# powerboard.net
KiCad netlist of a schematic drawn in EAGLE
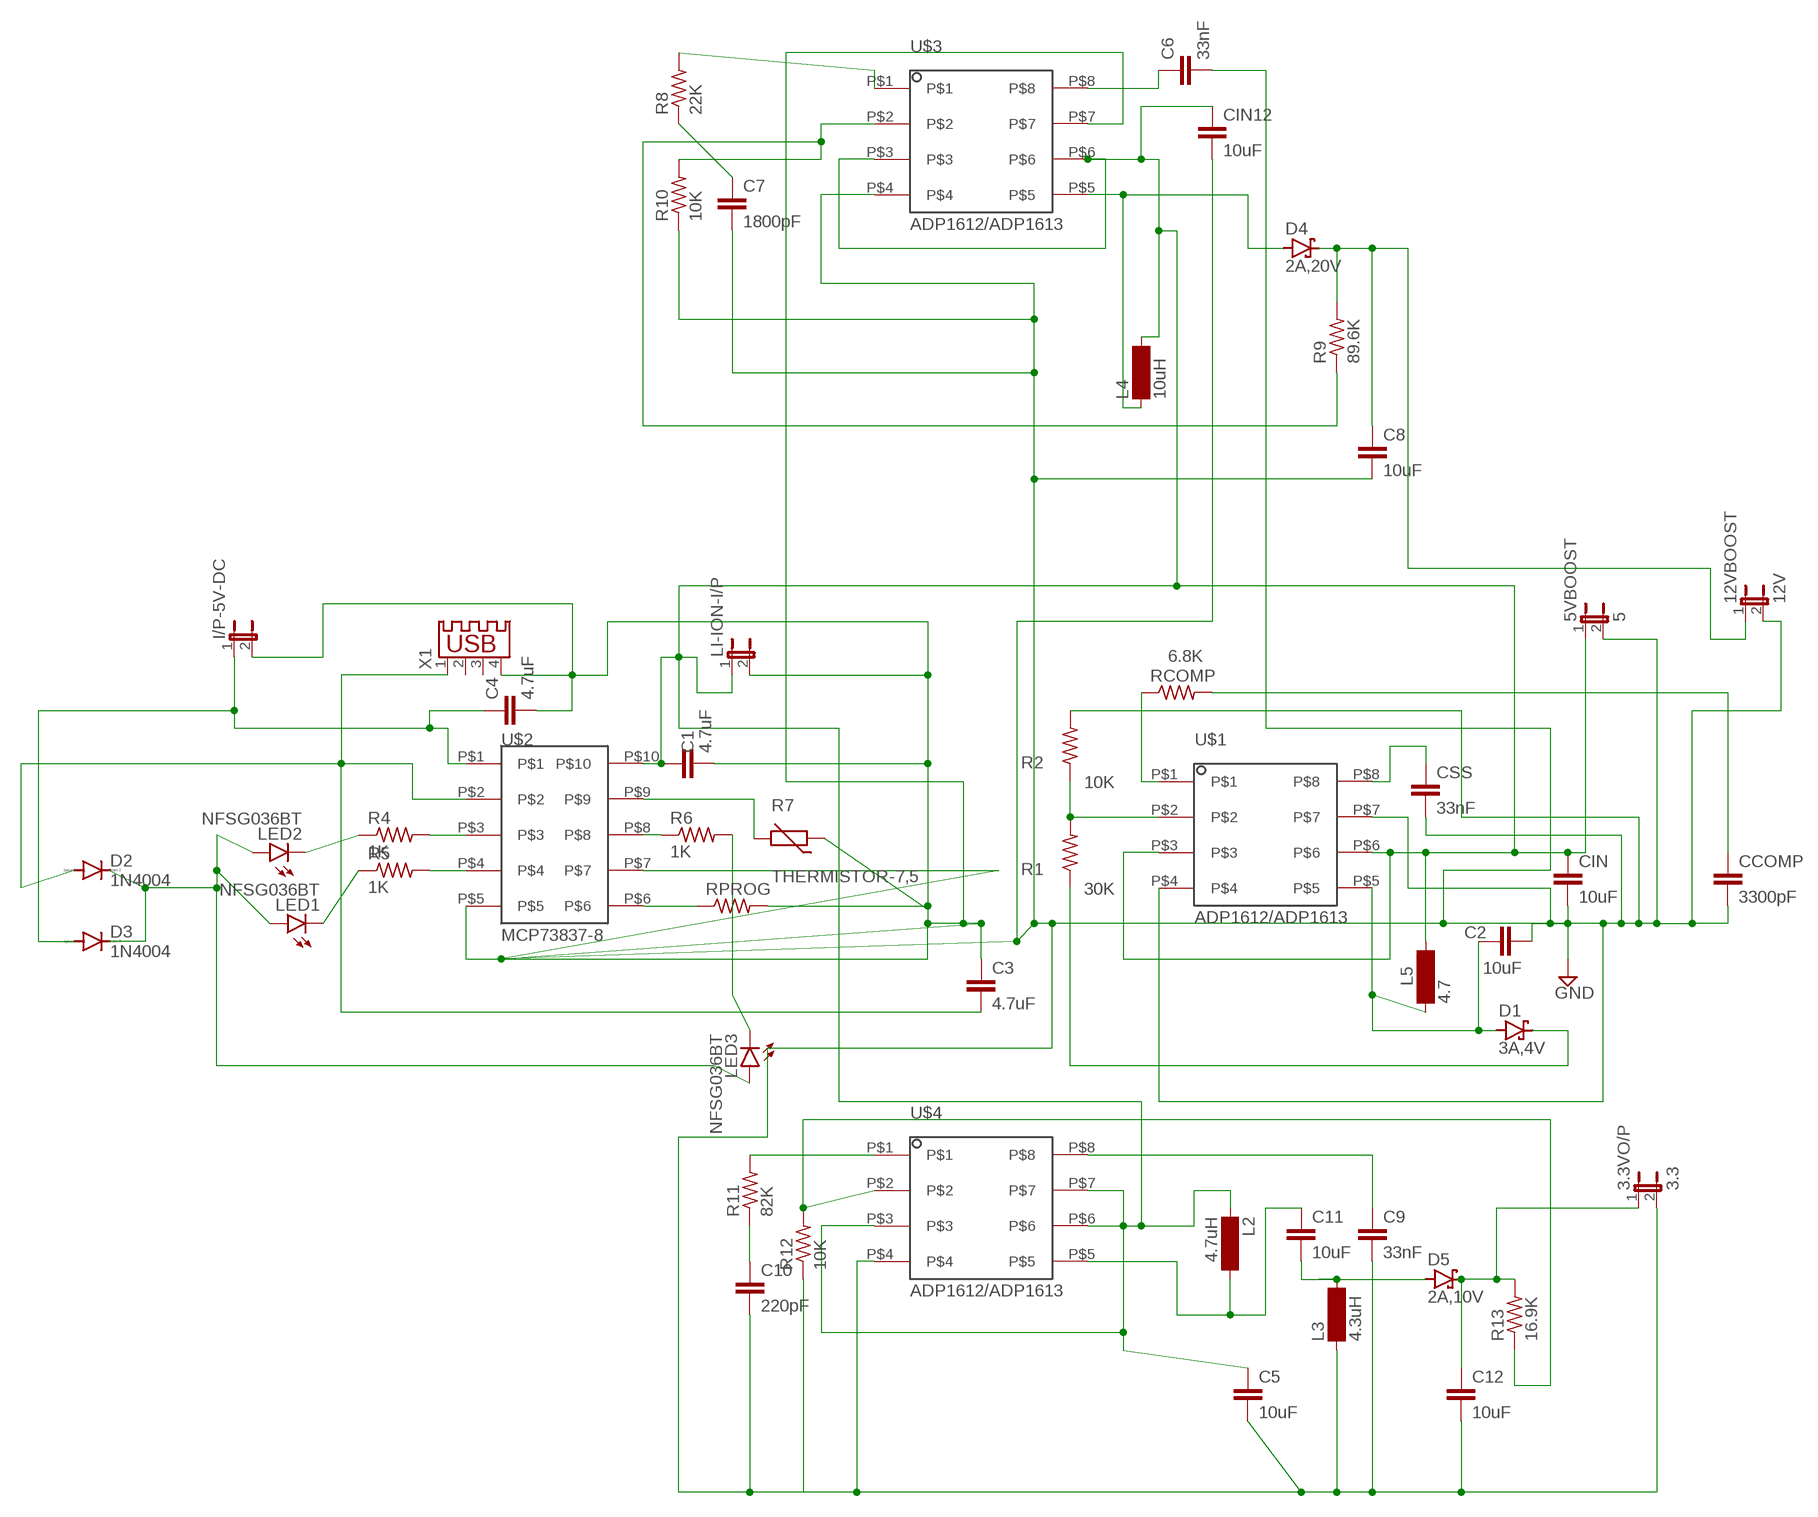
[diagram p0: schematic, sheet 1]

(export (version "E")
  (design (tool "Eeschema 10.0.6"))
  (components
    (comp (ref "3.3VO/P")
      (value "3.3")
      (footprint "eagle-import:JP1")
      (libsource (lib "eagle-import") (part "JP1E"))
    )
    (comp (ref "5VBOOST")
      (value "5")
      (footprint "eagle-import:JP1")
      (libsource (lib "eagle-import") (part "JP1E"))
    )
    (comp (ref "12VBOOST")
      (value "12V")
      (footprint "eagle-import:JP1")
      (libsource (lib "eagle-import") (part "JP1E"))
    )
    (comp (ref "C1")
      (value "4.7uF")
      (footprint "eagle-import:C2.5-3")
      (libsource (lib "eagle-import") (part "C2,5-3"))
    )
    (comp (ref "C2")
      (value "10uF")
      (footprint "eagle-import:C2.5-2")
      (libsource (lib "eagle-import") (part "C2.5/2"))
    )
    (comp (ref "C3")
      (value "4.7uF")
      (footprint "eagle-import:C2.5-3")
      (libsource (lib "eagle-import") (part "C2,5-3"))
    )
    (comp (ref "C4")
      (value "4.7uF")
      (footprint "eagle-import:C2.5-3")
      (libsource (lib "eagle-import") (part "C2,5-3"))
    )
    (comp (ref "C5")
      (value "10uF")
      (footprint "eagle-import:C2.5-2")
      (libsource (lib "eagle-import") (part "C2.5/2"))
    )
    (comp (ref "C6")
      (value "33nF")
      (footprint "eagle-import:C2.5-3")
      (libsource (lib "eagle-import") (part "C2,5-3"))
    )
    (comp (ref "C7")
      (value "1800pF")
      (footprint "eagle-import:C2.5-3")
      (libsource (lib "eagle-import") (part "C2,5-3"))
    )
    (comp (ref "C8")
      (value "10uF")
      (footprint "eagle-import:C2.5-3")
      (libsource (lib "eagle-import") (part "C2,5-3"))
    )
    (comp (ref "C9")
      (value "33nF")
      (footprint "eagle-import:C2.5-2")
      (libsource (lib "eagle-import") (part "C2.5/2"))
    )
    (comp (ref "C10")
      (value "220pF")
      (footprint "eagle-import:C2.5-2")
      (libsource (lib "eagle-import") (part "C2.5/2"))
    )
    (comp (ref "C11")
      (value "10uF")
      (footprint "eagle-import:C2.5-2")
      (libsource (lib "eagle-import") (part "C2.5/2"))
    )
    (comp (ref "C12")
      (value "10uF")
      (footprint "eagle-import:C2.5-2")
      (libsource (lib "eagle-import") (part "C2.5/2"))
    )
    (comp (ref "CCOMP")
      (value "3300pF")
      (footprint "eagle-import:C2.5-2")
      (libsource (lib "eagle-import") (part "C2.5/2"))
    )
    (comp (ref "CIN")
      (value "10uF")
      (footprint "eagle-import:C2.5-3")
      (libsource (lib "eagle-import") (part "C2,5-3"))
    )
    (comp (ref "CIN12")
      (value "10uF")
      (footprint "eagle-import:C2.5-3")
      (libsource (lib "eagle-import") (part "C2,5-3"))
    )
    (comp (ref "CSS")
      (value "33nF")
      (footprint "eagle-import:C2.5-2")
      (libsource (lib "eagle-import") (part "C2.5/2"))
    )
    (comp (ref "D1")
      (value "3A,4V")
      (footprint "eagle-import:DO35-7")
      (libsource (lib "eagle-import") (part "SCHOTTKY-DIODEDO35-7"))
    )
    (comp (ref "D2")
      (value "1N4004")
      (footprint "eagle-import:DO41-10")
      (libsource (lib "eagle-import") (part "1N4004"))
    )
    (comp (ref "D3")
      (value "1N4004")
      (footprint "eagle-import:DO41-10")
      (libsource (lib "eagle-import") (part "1N4004"))
    )
    (comp (ref "D4")
      (value "2A,20V")
      (footprint "eagle-import:DO35-7")
      (libsource (lib "eagle-import") (part "SCHOTTKY-DIODEDO35-7"))
    )
    (comp (ref "D5")
      (value "2A,10V")
      (footprint "eagle-import:DO35-7")
      (libsource (lib "eagle-import") (part "SCHOTTKY-DIODEDO35-7"))
    )
    (comp (ref "I/P-5V-DC")
      (value "JP1E")
      (footprint "eagle-import:JP1")
      (libsource (lib "eagle-import") (part "JP1E"))
    )
    (comp (ref "L2")
      (value "4.7uH")
      (footprint "eagle-import:BS75")
      (libsource (lib "eagle-import") (part "BS75"))
    )
    (comp (ref "L3")
      (value "4.3uH")
      (footprint "eagle-import:BS75")
      (libsource (lib "eagle-import") (part "BS75"))
    )
    (comp (ref "L4")
      (value "10uH")
      (footprint "eagle-import:BS75")
      (libsource (lib "eagle-import") (part "BS75"))
    )
    (comp (ref "L5")
      (value "4.7")
      (footprint "eagle-import:BS75")
      (libsource (lib "eagle-import") (part "BS75"))
    )
    (comp (ref "LED1")
      (value "NFSG036BT")
      (footprint "eagle-import:NFSG036BT")
      (libsource (lib "eagle-import") (part "NFSG036BT"))
    )
    (comp (ref "LED2")
      (value "NFSG036BT")
      (footprint "eagle-import:NFSG036BT")
      (libsource (lib "eagle-import") (part "NFSG036BT"))
    )
    (comp (ref "LED3")
      (value "NFSG036BT")
      (footprint "eagle-import:NFSG036BT")
      (libsource (lib "eagle-import") (part "NFSG036BT"))
    )
    (comp (ref "LI-ION-I/P")
      (value "JP1E")
      (footprint "eagle-import:JP1")
      (libsource (lib "eagle-import") (part "JP1E"))
    )
    (comp (ref "R1")
      (value "30K")
      (footprint "eagle-import:0207_10")
      (libsource (lib "eagle-import") (part "R-US_0207/10"))
    )
    (comp (ref "R2")
      (value "10K")
      (footprint "eagle-import:0207_10")
      (libsource (lib "eagle-import") (part "R-US_0207/10"))
    )
    (comp (ref "R4")
      (value "1K")
      (footprint "eagle-import:R0805")
      (libsource (lib "eagle-import") (part "R-US_R0805"))
    )
    (comp (ref "R5")
      (value "1K")
      (footprint "eagle-import:R0805")
      (libsource (lib "eagle-import") (part "R-US_R0805"))
    )
    (comp (ref "R6")
      (value "1K")
      (footprint "eagle-import:R0805")
      (libsource (lib "eagle-import") (part "R-US_R0805"))
    )
    (comp (ref "R7")
      (value "THERMISTOR-7,5")
      (footprint "eagle-import:R-7,5")
      (libsource (lib "eagle-import") (part "THERMISTOR-7,5"))
    )
    (comp (ref "R8")
      (value "22K")
      (footprint "eagle-import:0204_7")
      (libsource (lib "eagle-import") (part "R-US_0204/7"))
    )
    (comp (ref "R9")
      (value "89.6K")
      (footprint "eagle-import:0204_7")
      (libsource (lib "eagle-import") (part "R-US_0204/7"))
    )
    (comp (ref "R10")
      (value "10K")
      (footprint "eagle-import:0204_7")
      (libsource (lib "eagle-import") (part "R-US_0204/7"))
    )
    (comp (ref "R11")
      (value "82K")
      (footprint "eagle-import:0204_7")
      (libsource (lib "eagle-import") (part "R-US_0204/7"))
    )
    (comp (ref "R12")
      (value "10K")
      (footprint "eagle-import:0204_7")
      (libsource (lib "eagle-import") (part "R-US_0204/7"))
    )
    (comp (ref "R13")
      (value "16.9K")
      (footprint "eagle-import:0204_7")
      (libsource (lib "eagle-import") (part "R-US_0204/7"))
    )
    (comp (ref "RCOMP")
      (value "6.8K")
      (footprint "eagle-import:0207_10")
      (libsource (lib "eagle-import") (part "R-US_0207/10"))
    )
    (comp (ref "RPROG")
      (value "R-US_R0805")
      (footprint "eagle-import:R0805")
      (libsource (lib "eagle-import") (part "R-US_R0805"))
    )
    (comp (ref "U$1")
      (value "ADP1612/ADP1613")
      (footprint "eagle-import:ADP1612_ADP1613")
      (libsource (lib "eagle-import") (part "ADP1612/ADP1613"))
    )
    (comp (ref "U$2")
      (value "MCP73837-8")
      (footprint "eagle-import:MCP73837_8")
      (libsource (lib "eagle-import") (part "MCP73837-8"))
    )
    (comp (ref "U$3")
      (value "ADP1612/ADP1613")
      (footprint "eagle-import:ADP1612_ADP1613")
      (libsource (lib "eagle-import") (part "ADP1612/ADP1613"))
    )
    (comp (ref "U$4")
      (value "ADP1612/ADP1613")
      (footprint "eagle-import:ADP1612_ADP1613")
      (libsource (lib "eagle-import") (part "ADP1612/ADP1613"))
    )
    (comp (ref "X1")
      (value "USB-A003")
      (footprint "eagle-import:USB-A003")
      (libsource (lib "eagle-import") (part "USB-A003"))
    )
  )
  (nets
    (net (code "1") (name "GND") (class "Default")
      (node (ref "12VBOOST") (pin "2") (pinfunction "2_2") (pintype "passive"))
      (node (ref "3.3VO/P") (pin "2") (pinfunction "2_2") (pintype "passive"))
      (node (ref "5VBOOST") (pin "2") (pinfunction "2_2") (pintype "passive"))
      (node (ref "C1") (pin "2") (pinfunction "2_2") (pintype "passive"))
      (node (ref "C10") (pin "2") (pinfunction "2_2") (pintype "passive"))
      (node (ref "C12") (pin "2") (pinfunction "2_2") (pintype "passive"))
      (node (ref "C2") (pin "2") (pinfunction "2_2") (pintype "passive"))
      (node (ref "C3") (pin "1") (pinfunction "1_1") (pintype "passive"))
      (node (ref "C4") (pin "2") (pinfunction "2_2") (pintype "passive"))
      (node (ref "C5") (pin "2") (pinfunction "2_2") (pintype "passive"))
      (node (ref "C6") (pin "2") (pinfunction "2_2") (pintype "passive"))
      (node (ref "C7") (pin "2") (pinfunction "2_2") (pintype "passive"))
      (node (ref "C8") (pin "2") (pinfunction "2_2") (pintype "passive"))
      (node (ref "C9") (pin "2") (pinfunction "2_2") (pintype "passive"))
      (node (ref "CCOMP") (pin "2") (pinfunction "2_2") (pintype "passive"))
      (node (ref "CIN") (pin "2") (pinfunction "2_2") (pintype "passive"))
      (node (ref "CIN12") (pin "2") (pinfunction "2_2") (pintype "passive"))
      (node (ref "CSS") (pin "2") (pinfunction "2_2") (pintype "passive"))
      (node (ref "I/P-5V-DC") (pin "2") (pinfunction "2_2") (pintype "passive"))
      (node (ref "L3") (pin "1") (pinfunction "1_1") (pintype "passive"))
      (node (ref "LI-ION-I/P") (pin "2") (pinfunction "2_2") (pintype "passive"))
      (node (ref "R10") (pin "1") (pinfunction "1_1") (pintype "passive"))
      (node (ref "R12") (pin "1") (pinfunction "1_1") (pintype "passive"))
      (node (ref "R2") (pin "2") (pinfunction "2_2") (pintype "passive"))
      (node (ref "R7") (pin "1") (pinfunction "1_1") (pintype "passive"))
      (node (ref "RPROG") (pin "2") (pinfunction "2_2") (pintype "passive"))
      (node (ref "U$1") (pin "P$4") (pinfunction "P$4_P$4") (pintype "bidirectional"))
      (node (ref "U$1") (pin "P$7") (pinfunction "P$7_P$7") (pintype "bidirectional"))
      (node (ref "U$2") (pin "P$5") (pinfunction "P$5_P$5") (pintype "bidirectional"))
      (node (ref "U$2") (pin "P$7") (pinfunction "P$7_P$7") (pintype "bidirectional"))
      (node (ref "U$3") (pin "P$4") (pinfunction "P$4_P$4") (pintype "bidirectional"))
      (node (ref "U$3") (pin "P$7") (pinfunction "P$7_P$7") (pintype "bidirectional"))
      (node (ref "U$4") (pin "P$4") (pinfunction "P$4_P$4") (pintype "bidirectional"))
      (node (ref "X1") (pin "4") (pinfunction "4_4") (pintype "passive"))
    )
    (net (code "2") (name "Net-(3.3VO/P-Pad1)") (class "Default")
      (node (ref "3.3VO/P") (pin "1") (pinfunction "1_1") (pintype "passive"))
      (node (ref "C12") (pin "1") (pinfunction "1_1") (pintype "passive"))
      (node (ref "D5") (pin "C") (pinfunction "C_C") (pintype "passive"))
      (node (ref "R13") (pin "2") (pinfunction "2_2") (pintype "passive"))
    )
    (net (code "3") (name "Net-(5VBOOST-Pad1)") (class "Default")
      (node (ref "5VBOOST") (pin "1") (pinfunction "1_1") (pintype "passive"))
      (node (ref "C1") (pin "1") (pinfunction "1_1") (pintype "passive"))
      (node (ref "C5") (pin "1") (pinfunction "1_1") (pintype "passive"))
      (node (ref "CIN") (pin "1") (pinfunction "1_1") (pintype "passive"))
      (node (ref "CIN12") (pin "1") (pinfunction "1_1") (pintype "passive"))
      (node (ref "L2") (pin "1") (pinfunction "1_1") (pintype "passive"))
      (node (ref "L4") (pin "2") (pinfunction "2_2") (pintype "passive"))
      (node (ref "L5") (pin "2") (pinfunction "2_2") (pintype "passive"))
      (node (ref "LI-ION-I/P") (pin "1") (pinfunction "1_1") (pintype "passive"))
      (node (ref "U$1") (pin "P$3") (pinfunction "P$3_P$3") (pintype "bidirectional"))
      (node (ref "U$1") (pin "P$6") (pinfunction "P$6_P$6") (pintype "bidirectional"))
      (node (ref "U$2") (pin "P$10") (pinfunction "P$10_P$10") (pintype "bidirectional"))
      (node (ref "U$3") (pin "P$3") (pinfunction "P$3_P$3") (pintype "bidirectional"))
      (node (ref "U$3") (pin "P$6") (pinfunction "P$6_P$6") (pintype "bidirectional"))
      (node (ref "U$4") (pin "P$3") (pinfunction "P$3_P$3") (pintype "bidirectional"))
      (node (ref "U$4") (pin "P$6") (pinfunction "P$6_P$6") (pintype "bidirectional"))
      (node (ref "U$4") (pin "P$7") (pinfunction "P$7_P$7") (pintype "bidirectional"))
    )
    (net (code "4") (name "Net-(12VBOOST-Pad1)") (class "Default")
      (node (ref "12VBOOST") (pin "1") (pinfunction "1_1") (pintype "passive"))
      (node (ref "C8") (pin "1") (pinfunction "1_1") (pintype "passive"))
      (node (ref "D4") (pin "C") (pinfunction "C_C") (pintype "passive"))
      (node (ref "R9") (pin "2") (pinfunction "2_2") (pintype "passive"))
    )
    (net (code "5") (name "Net-(C2-Pad1)") (class "Default")
      (node (ref "C2") (pin "1") (pinfunction "1_1") (pintype "passive"))
      (node (ref "D1") (pin "A") (pinfunction "A_A") (pintype "passive"))
      (node (ref "L5") (pin "1") (pinfunction "1_1") (pintype "passive"))
      (node (ref "U$1") (pin "P$5") (pinfunction "P$5_P$5") (pintype "bidirectional"))
    )
    (net (code "6") (name "Net-(C3-Pad2)") (class "Default")
      (node (ref "C3") (pin "2") (pinfunction "2_2") (pintype "passive"))
      (node (ref "D2") (pin "A") (pinfunction "A_A") (pintype "passive"))
      (node (ref "U$2") (pin "P$2") (pinfunction "P$2_P$2") (pintype "bidirectional"))
      (node (ref "X1") (pin "1") (pinfunction "1_1") (pintype "passive"))
    )
    (net (code "7") (name "Net-(C4-Pad1)") (class "Default")
      (node (ref "C4") (pin "1") (pinfunction "1_1") (pintype "passive"))
      (node (ref "D3") (pin "A") (pinfunction "A_A") (pintype "passive"))
      (node (ref "I/P-5V-DC") (pin "1") (pinfunction "1_1") (pintype "passive"))
      (node (ref "U$2") (pin "P$1") (pinfunction "P$1_P$1") (pintype "bidirectional"))
    )
    (net (code "8") (name "Net-(C6-Pad1)") (class "Default")
      (node (ref "C6") (pin "1") (pinfunction "1_1") (pintype "passive"))
      (node (ref "U$3") (pin "P$8") (pinfunction "P$8_P$8") (pintype "bidirectional"))
    )
    (net (code "9") (name "Net-(C7-Pad1)") (class "Default")
      (node (ref "C7") (pin "1") (pinfunction "1_1") (pintype "passive"))
      (node (ref "R8") (pin "1") (pinfunction "1_1") (pintype "passive"))
    )
    (net (code "10") (name "Net-(C9-Pad1)") (class "Default")
      (node (ref "C9") (pin "1") (pinfunction "1_1") (pintype "passive"))
      (node (ref "U$4") (pin "P$8") (pinfunction "P$8_P$8") (pintype "bidirectional"))
    )
    (net (code "11") (name "Net-(C10-Pad1)") (class "Default")
      (node (ref "C10") (pin "1") (pinfunction "1_1") (pintype "passive"))
      (node (ref "R11") (pin "1") (pinfunction "1_1") (pintype "passive"))
    )
    (net (code "12") (name "Net-(C11-Pad1)") (class "Default")
      (node (ref "C11") (pin "1") (pinfunction "1_1") (pintype "passive"))
      (node (ref "L2") (pin "2") (pinfunction "2_2") (pintype "passive"))
      (node (ref "U$4") (pin "P$5") (pinfunction "P$5_P$5") (pintype "bidirectional"))
    )
    (net (code "13") (name "Net-(C11-Pad2)") (class "Default")
      (node (ref "C11") (pin "2") (pinfunction "2_2") (pintype "passive"))
      (node (ref "D5") (pin "A") (pinfunction "A_A") (pintype "passive"))
      (node (ref "L3") (pin "2") (pinfunction "2_2") (pintype "passive"))
    )
    (net (code "14") (name "Net-(CCOMP-Pad1)") (class "Default")
      (node (ref "CCOMP") (pin "1") (pinfunction "1_1") (pintype "passive"))
      (node (ref "RCOMP") (pin "2") (pinfunction "2_2") (pintype "passive"))
    )
    (net (code "15") (name "Net-(CSS-Pad1)") (class "Default")
      (node (ref "CSS") (pin "1") (pinfunction "1_1") (pintype "passive"))
      (node (ref "U$1") (pin "P$8") (pinfunction "P$8_P$8") (pintype "bidirectional"))
    )
    (net (code "16") (name "Net-(D1-PadC)") (class "Default")
      (node (ref "D1") (pin "C") (pinfunction "C_C") (pintype "passive"))
      (node (ref "R1") (pin "1") (pinfunction "1_1") (pintype "passive"))
    )
    (net (code "17") (name "Net-(D2-PadC)") (class "Default")
      (node (ref "D2") (pin "C") (pinfunction "C_C") (pintype "passive"))
      (node (ref "D3") (pin "C") (pinfunction "C_C") (pintype "passive"))
      (node (ref "LED1") (pin "A") (pinfunction "A_A") (pintype "passive"))
      (node (ref "LED2") (pin "A") (pinfunction "A_A") (pintype "passive"))
      (node (ref "LED3") (pin "A") (pinfunction "A_A") (pintype "passive"))
    )
    (net (code "18") (name "Net-(D4-PadA)") (class "Default")
      (node (ref "D4") (pin "A") (pinfunction "A_A") (pintype "passive"))
      (node (ref "L4") (pin "1") (pinfunction "1_1") (pintype "passive"))
      (node (ref "U$3") (pin "P$5") (pinfunction "P$5_P$5") (pintype "bidirectional"))
    )
    (net (code "19") (name "Net-(LED1-PadC)") (class "Default")
      (node (ref "LED1") (pin "C") (pinfunction "C_C") (pintype "passive"))
      (node (ref "R5") (pin "1") (pinfunction "1_1") (pintype "passive"))
    )
    (net (code "20") (name "Net-(LED2-PadC)") (class "Default")
      (node (ref "LED2") (pin "C") (pinfunction "C_C") (pintype "passive"))
      (node (ref "R4") (pin "1") (pinfunction "1_1") (pintype "passive"))
    )
    (net (code "21") (name "Net-(LED3-PadC)") (class "Default")
      (node (ref "LED3") (pin "C") (pinfunction "C_C") (pintype "passive"))
      (node (ref "R6") (pin "2") (pinfunction "2_2") (pintype "passive"))
    )
    (net (code "22") (name "Net-(R1-Pad2)") (class "Default")
      (node (ref "R1") (pin "2") (pinfunction "2_2") (pintype "passive"))
      (node (ref "R2") (pin "1") (pinfunction "1_1") (pintype "passive"))
      (node (ref "U$1") (pin "P$2") (pinfunction "P$2_P$2") (pintype "bidirectional"))
    )
    (net (code "23") (name "Net-(R4-Pad2)") (class "Default")
      (node (ref "R4") (pin "2") (pinfunction "2_2") (pintype "passive"))
      (node (ref "U$2") (pin "P$3") (pinfunction "P$3_P$3") (pintype "bidirectional"))
    )
    (net (code "24") (name "Net-(R5-Pad2)") (class "Default")
      (node (ref "R5") (pin "2") (pinfunction "2_2") (pintype "passive"))
      (node (ref "U$2") (pin "P$4") (pinfunction "P$4_P$4") (pintype "bidirectional"))
    )
    (net (code "25") (name "Net-(R6-Pad1)") (class "Default")
      (node (ref "R6") (pin "1") (pinfunction "1_1") (pintype "passive"))
      (node (ref "U$2") (pin "P$8") (pinfunction "P$8_P$8") (pintype "bidirectional"))
    )
    (net (code "26") (name "Net-(R7-Pad2)") (class "Default")
      (node (ref "R7") (pin "2") (pinfunction "2_2") (pintype "passive"))
      (node (ref "U$2") (pin "P$9") (pinfunction "P$9_P$9") (pintype "bidirectional"))
    )
    (net (code "27") (name "Net-(R8-Pad2)") (class "Default")
      (node (ref "R8") (pin "2") (pinfunction "2_2") (pintype "passive"))
      (node (ref "U$3") (pin "P$1") (pinfunction "P$1_P$1") (pintype "bidirectional"))
    )
    (net (code "28") (name "Net-(R10-Pad2)") (class "Default")
      (node (ref "R10") (pin "2") (pinfunction "2_2") (pintype "passive"))
      (node (ref "R9") (pin "1") (pinfunction "1_1") (pintype "passive"))
      (node (ref "U$3") (pin "P$2") (pinfunction "P$2_P$2") (pintype "bidirectional"))
    )
    (net (code "29") (name "Net-(R11-Pad2)") (class "Default")
      (node (ref "R11") (pin "2") (pinfunction "2_2") (pintype "passive"))
      (node (ref "U$4") (pin "P$1") (pinfunction "P$1_P$1") (pintype "bidirectional"))
    )
    (net (code "30") (name "Net-(R12-Pad2)") (class "Default")
      (node (ref "R12") (pin "2") (pinfunction "2_2") (pintype "passive"))
      (node (ref "R13") (pin "1") (pinfunction "1_1") (pintype "passive"))
      (node (ref "U$4") (pin "P$2") (pinfunction "P$2_P$2") (pintype "bidirectional"))
    )
    (net (code "31") (name "Net-(RCOMP-Pad1)") (class "Default")
      (node (ref "RCOMP") (pin "1") (pinfunction "1_1") (pintype "passive"))
      (node (ref "U$1") (pin "P$1") (pinfunction "P$1_P$1") (pintype "bidirectional"))
    )
    (net (code "32") (name "Net-(RPROG-Pad1)") (class "Default")
      (node (ref "RPROG") (pin "1") (pinfunction "1_1") (pintype "passive"))
      (node (ref "U$2") (pin "P$6") (pinfunction "P$6_P$6") (pintype "bidirectional"))
    )
    (net (code "33") (name "unconnected-(X1-Pad2)") (class "Default")
      (node (ref "X1") (pin "2") (pinfunction "2_2") (pintype "passive"))
    )
    (net (code "34") (name "unconnected-(X1-Pad3)") (class "Default")
      (node (ref "X1") (pin "3") (pinfunction "3_3") (pintype "passive"))
    )
  )
)
